# ESPDRONE2_1.net
KiCad netlist of a schematic drawn in EAGLE
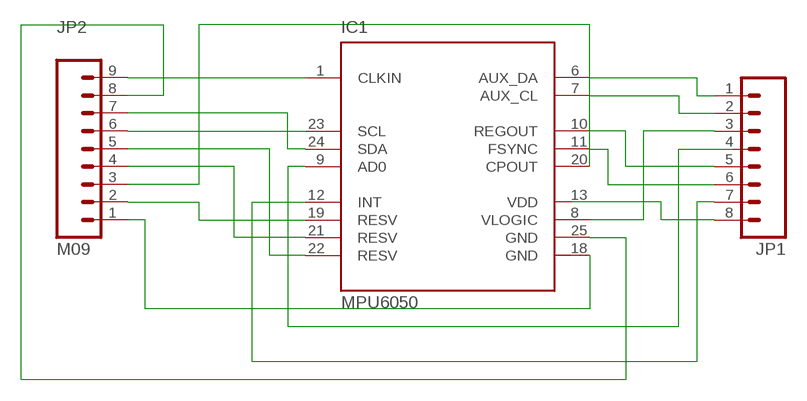
[diagram p0: schematic, sheet 1]

(export (version "E")
  (design (tool "Eeschema 10.0.6"))
  (components
    (comp (ref "IC1")
      (value "MPU6050")
      (footprint "eagle-import:QFN50P400X400X95-25T265X275N")
      (libsource (lib "eagle-import") (part "MPU6050"))
    )
    (comp (ref "JP1")
      (value "M081X08")
      (footprint "eagle-import:1X08")
      (libsource (lib "eagle-import") (part "M081X08"))
    )
    (comp (ref "JP2")
      (value "M09")
      (footprint "eagle-import:1X09")
      (libsource (lib "eagle-import") (part "M09"))
    )
  )
  (nets
    (net (code "1") (name "/VDD") (class "Default")
      (node (ref "IC1") (pin "13") (pinfunction "VDD_13") (pintype "power_in"))
    )
    (net (code "2") (name "Net-(IC1A-AUX_CL)") (class "Default")
      (node (ref "IC1") (pin "7") (pinfunction "AUX_CL_7") (pintype "bidirectional"))
      (node (ref "JP1") (pin "2") (pinfunction "2_2") (pintype "passive"))
    )
    (net (code "3") (name "Net-(IC1A-AUX_DA)") (class "Default")
      (node (ref "IC1") (pin "6") (pinfunction "AUX_DA_6") (pintype "bidirectional"))
      (node (ref "JP1") (pin "1") (pinfunction "1_1") (pintype "passive"))
    )
    (net (code "4") (name "Net-(IC1A-CLKIN)") (class "Default")
      (node (ref "IC1") (pin "1") (pinfunction "CLKIN_1") (pintype "input"))
      (node (ref "JP2") (pin "9") (pinfunction "9_9") (pintype "passive"))
    )
    (net (code "5") (name "Net-(IC1A-CPOUT)") (class "Default")
      (node (ref "IC1") (pin "20") (pinfunction "CPOUT_20") (pintype "output"))
      (node (ref "JP2") (pin "3") (pinfunction "3_3") (pintype "passive"))
    )
    (net (code "6") (name "Net-(IC1A-FSYNC)") (class "Default")
      (node (ref "IC1") (pin "11") (pinfunction "FSYNC_11") (pintype "input"))
      (node (ref "JP1") (pin "6") (pinfunction "6_6") (pintype "passive"))
    )
    (net (code "7") (name "Net-(IC1A-GND-Pad18)") (class "Default")
      (node (ref "IC1") (pin "18") (pinfunction "GND_18") (pintype "power_in"))
      (node (ref "JP2") (pin "1") (pinfunction "1_1") (pintype "passive"))
    )
    (net (code "8") (name "Net-(IC1A-GND-Pad25)") (class "Default")
      (node (ref "IC1") (pin "25") (pinfunction "GND_25") (pintype "power_in"))
      (node (ref "JP2") (pin "8") (pinfunction "8_8") (pintype "passive"))
    )
    (net (code "9") (name "Net-(IC1A-INT)") (class "Default")
      (node (ref "IC1") (pin "12") (pinfunction "INT_12") (pintype "open_collector"))
      (node (ref "JP1") (pin "7") (pinfunction "7_7") (pintype "passive"))
    )
    (net (code "10") (name "Net-(IC1A-REGOUT)") (class "Default")
      (node (ref "IC1") (pin "10") (pinfunction "REGOUT_10") (pintype "output"))
      (node (ref "JP1") (pin "5") (pinfunction "5_5") (pintype "passive"))
    )
    (net (code "11") (name "Net-(IC1A-RESV-Pad19)") (class "Default")
      (node (ref "IC1") (pin "19") (pinfunction "RESV_19") (pintype "passive"))
      (node (ref "JP2") (pin "2") (pinfunction "2_2") (pintype "passive"))
    )
    (net (code "12") (name "Net-(IC1A-RESV-Pad21)") (class "Default")
      (node (ref "IC1") (pin "21") (pinfunction "RESV_21") (pintype "passive"))
      (node (ref "JP2") (pin "4") (pinfunction "4_4") (pintype "passive"))
    )
    (net (code "13") (name "Net-(IC1A-RESV-Pad22)") (class "Default")
      (node (ref "IC1") (pin "22") (pinfunction "RESV_22") (pintype "passive"))
      (node (ref "JP2") (pin "5") (pinfunction "5_5") (pintype "passive"))
    )
    (net (code "14") (name "Net-(IC1A-SCL)") (class "Default")
      (node (ref "IC1") (pin "23") (pinfunction "SCL_23") (pintype "input"))
      (node (ref "JP2") (pin "6") (pinfunction "6_6") (pintype "passive"))
    )
    (net (code "15") (name "Net-(IC1A-SDA)") (class "Default")
      (node (ref "IC1") (pin "24") (pinfunction "SDA_24") (pintype "bidirectional"))
      (node (ref "JP2") (pin "7") (pinfunction "7_7") (pintype "passive"))
    )
    (net (code "16") (name "Net-(IC1A-VLOGIC)") (class "Default")
      (node (ref "IC1") (pin "8") (pinfunction "VLOGIC_8") (pintype "power_in"))
      (node (ref "JP1") (pin "3") (pinfunction "3_3") (pintype "passive"))
    )
    (net (code "17") (name "unconnected-(IC1A-AD0-Pad9)") (class "Default")
      (node (ref "IC1") (pin "9") (pinfunction "AD0_9") (pintype "input"))
    )
    (net (code "18") (name "unconnected-(JP1-Pad4)") (class "Default")
      (node (ref "JP1") (pin "4") (pinfunction "4_4") (pintype "passive"))
    )
    (net (code "19") (name "unconnected-(JP1-Pad8)") (class "Default")
      (node (ref "JP1") (pin "8") (pinfunction "8_8") (pintype "passive"))
    )
  )
)
